# SHT1x-Breakout.net
KiCad netlist of a schematic drawn in EAGLE
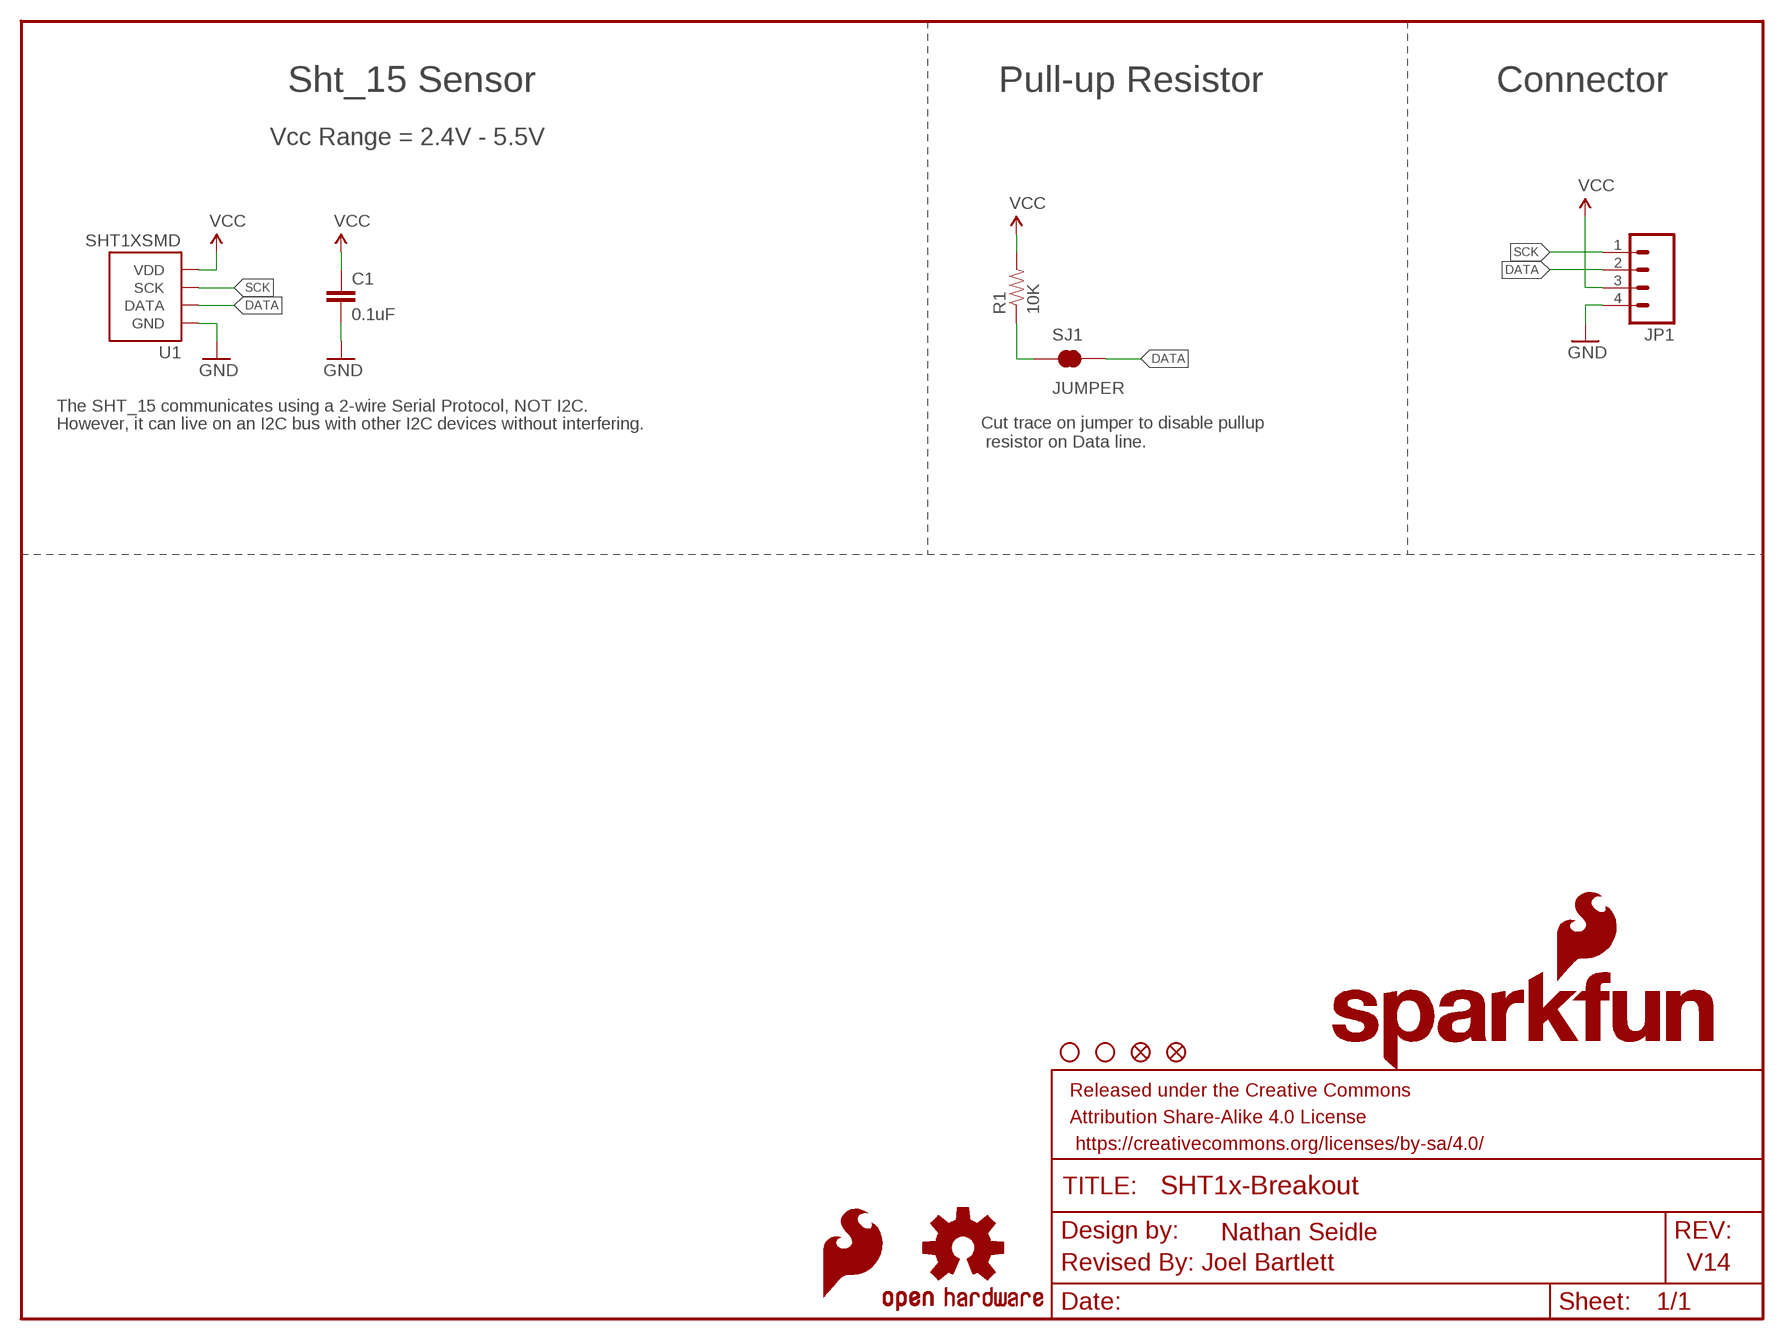
[diagram p0: schematic, sheet 1]

(export (version "E")
  (design (tool "Eeschema 10.0.6"))
  (components
    (comp (ref "C1")
      (value "0.1uF")
      (footprint "eagle-import:0603-CAP")
      (libsource (lib "eagle-import") (part "0.1UF-25V(+80/-20%)(0603)"))
    )
    (comp (ref "FID1")
      (value "FIDUCIAL1X2")
      (footprint "eagle-import:FIDUCIAL-1X2")
      (libsource (lib "eagle-import") (part "FIDUCIAL1X2"))
    )
    (comp (ref "FID2")
      (value "FIDUCIAL1X2")
      (footprint "eagle-import:FIDUCIAL-1X2")
      (libsource (lib "eagle-import") (part "FIDUCIAL1X2"))
    )
    (comp (ref "FRAME1")
      (value "FRAME-LETTER")
      (footprint "eagle-import:CREATIVE_COMMONS")
      (libsource (lib "eagle-import") (part "FRAME-LETTER"))
    )
    (comp (ref "JP1")
      (value "M04PTH")
      (footprint "eagle-import:1X04")
      (libsource (lib "eagle-import") (part "M04PTH"))
    )
    (comp (ref "LOGO1")
      (value "OSHW-LOGOS")
      (footprint "eagle-import:OSHW-LOGO-S")
      (libsource (lib "eagle-import") (part "OSHW-LOGOS"))
    )
    (comp (ref "LOGO2")
      (value "SFE_LOGO_NAME.1_INCH")
      (footprint "eagle-import:SFE_LOGO_NAME_.1")
      (libsource (lib "eagle-import") (part "SFE_LOGO_NAME.1_INCH"))
    )
    (comp (ref "LOGO4")
      (value "SFE_LOGO_FLAME.1_INCH")
      (footprint "eagle-import:SFE_LOGO_FLAME_.1")
      (libsource (lib "eagle-import") (part "SFE_LOGO_FLAME.1_INCH"))
    )
    (comp (ref "LOGO5")
      (value "SFE_LOGO_NAME_FLAME.1_INCH")
      (footprint "eagle-import:SFE_LOGO_NAME_FLAME_.1")
      (libsource (lib "eagle-import") (part "SFE_LOGO_NAME_FLAME.1_INCH"))
    )
    (comp (ref "R1")
      (value "10K")
      (footprint "eagle-import:0603-RES")
      (libsource (lib "eagle-import") (part "10KOHM-1/10W-1%(0603)0603"))
    )
    (comp (ref "SJ1")
      (value "JUMPER")
      (footprint "eagle-import:PAD-JUMPER-2-NC_BY_TRACE_YES_SILK")
      (libsource (lib "eagle-import") (part "JUMPER-PAD-2-NC_BY_TRACE"))
    )
    (comp (ref "STANDOFF1")
      (value "STAND-OFF")
      (footprint "eagle-import:STAND-OFF")
      (libsource (lib "eagle-import") (part "STAND-OFF"))
    )
    (comp (ref "STANDOFF2")
      (value "STAND-OFF")
      (footprint "eagle-import:STAND-OFF")
      (libsource (lib "eagle-import") (part "STAND-OFF"))
    )
    (comp (ref "U1")
      (value "SHT1XSMD")
      (footprint "eagle-import:SHT1X")
      (libsource (lib "eagle-import") (part "SHT1XSMD"))
    )
  )
  (nets
    (net (code "1") (name "DATA") (class "Default")
      (node (ref "JP1") (pin "2") (pinfunction "2_2") (pintype "passive"))
      (node (ref "SJ1") (pin "2") (pinfunction "2_2") (pintype "passive"))
      (node (ref "U1") (pin "2") (pinfunction "DATA_2") (pintype "bidirectional"))
    )
    (net (code "2") (name "GND") (class "Default")
      (node (ref "C1") (pin "2") (pinfunction "2_2") (pintype "passive"))
      (node (ref "JP1") (pin "4") (pinfunction "4_4") (pintype "passive"))
      (node (ref "U1") (pin "1") (pinfunction "GND_1") (pintype "power_in"))
    )
    (net (code "3") (name "Net-(R1-Pad1)") (class "Default")
      (node (ref "R1") (pin "1") (pinfunction "1_1") (pintype "passive"))
      (node (ref "SJ1") (pin "1") (pinfunction "1_1") (pintype "passive"))
    )
    (net (code "4") (name "SCK") (class "Default")
      (node (ref "JP1") (pin "1") (pinfunction "1_1") (pintype "passive"))
      (node (ref "U1") (pin "3") (pinfunction "SCK_3") (pintype "input"))
    )
    (net (code "5") (name "VCC") (class "Default")
      (node (ref "C1") (pin "1") (pinfunction "1_1") (pintype "passive"))
      (node (ref "JP1") (pin "3") (pinfunction "3_3") (pintype "passive"))
      (node (ref "R1") (pin "2") (pinfunction "2_2") (pintype "passive"))
      (node (ref "U1") (pin "4") (pinfunction "VDD_4") (pintype "power_in"))
    )
  )
)
